# SUSTAINA-Power-Logging-Board.net
KiCad netlist of a schematic drawn in EAGLE
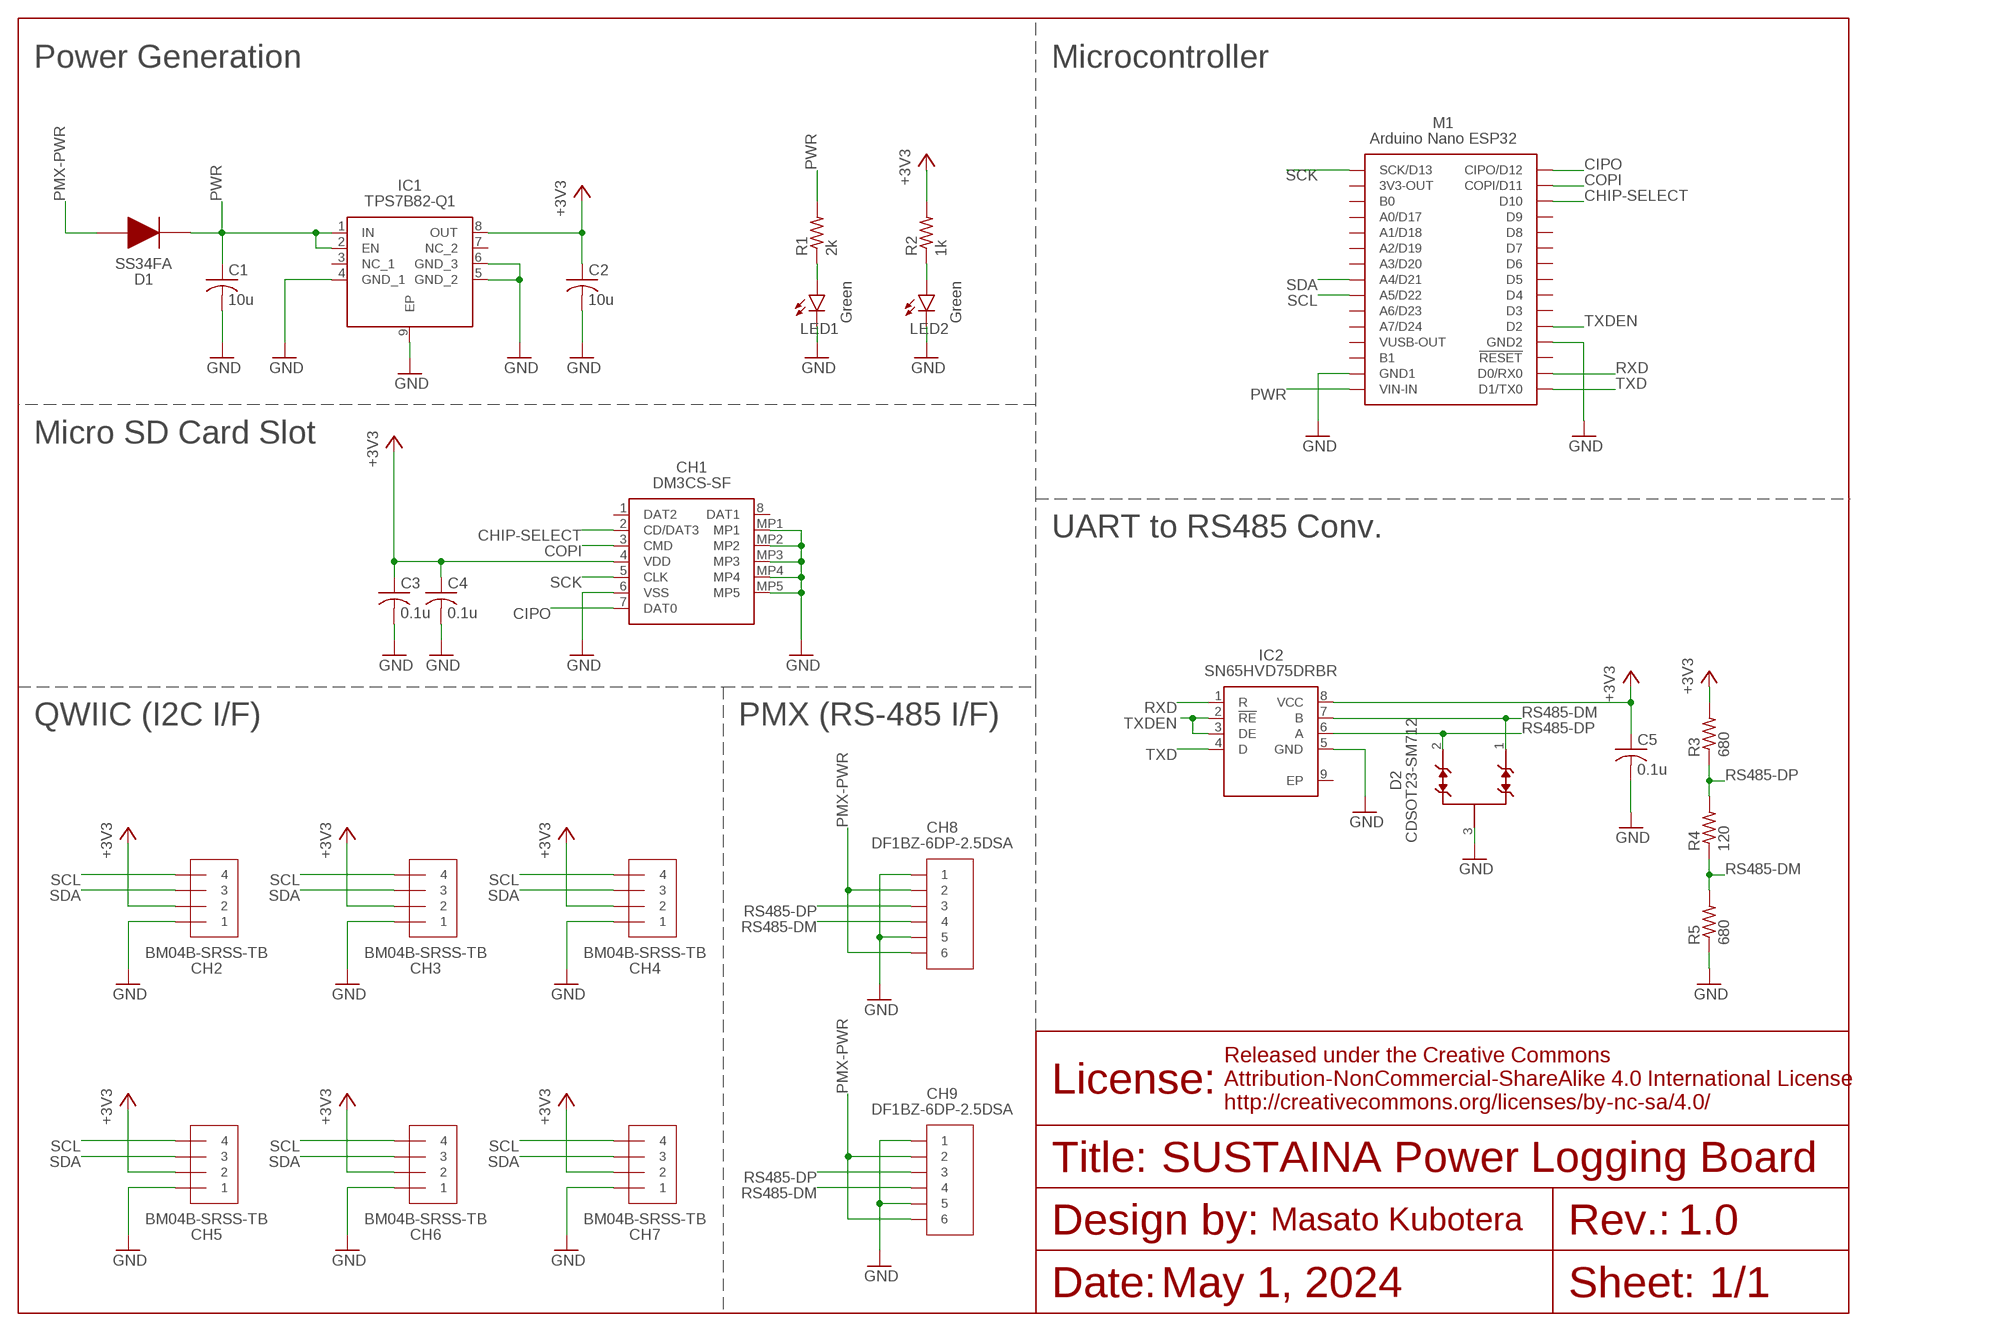
[diagram p0: schematic, sheet 1]

(export (version "E")
  (design (tool "Eeschema 10.0.6"))
  (components
    (comp (ref "C1")
      (value "10u")
      (footprint "eagle-import:C0603")
      (libsource (lib "eagle-import") (part "C-USC0603"))
    )
    (comp (ref "C2")
      (value "10u")
      (footprint "eagle-import:C0603")
      (libsource (lib "eagle-import") (part "C-USC0603"))
    )
    (comp (ref "C3")
      (value "0.1u")
      (footprint "eagle-import:C0603")
      (libsource (lib "eagle-import") (part "C-USC0603"))
    )
    (comp (ref "C4")
      (value "0.1u")
      (footprint "eagle-import:C0603")
      (libsource (lib "eagle-import") (part "C-USC0603"))
    )
    (comp (ref "C5")
      (value "0.1u")
      (footprint "eagle-import:C0603")
      (libsource (lib "eagle-import") (part "C-USC0603"))
    )
    (comp (ref "CH1")
      (value "DM3CS-SF")
      (footprint "eagle-import:DM3CS-SF")
      (libsource (lib "eagle-import") (part "DM3CS-SF"))
    )
    (comp (ref "CH2")
      (value "BM04B-SRSS-TB")
      (footprint "eagle-import:BM04B-SRSS-TB")
      (libsource (lib "eagle-import") (part "BM04B-SRSS-TB"))
    )
    (comp (ref "CH3")
      (value "BM04B-SRSS-TB")
      (footprint "eagle-import:BM04B-SRSS-TB")
      (libsource (lib "eagle-import") (part "BM04B-SRSS-TB"))
    )
    (comp (ref "CH4")
      (value "BM04B-SRSS-TB")
      (footprint "eagle-import:BM04B-SRSS-TB")
      (libsource (lib "eagle-import") (part "BM04B-SRSS-TB"))
    )
    (comp (ref "CH5")
      (value "BM04B-SRSS-TB")
      (footprint "eagle-import:BM04B-SRSS-TB")
      (libsource (lib "eagle-import") (part "BM04B-SRSS-TB"))
    )
    (comp (ref "CH6")
      (value "BM04B-SRSS-TB")
      (footprint "eagle-import:BM04B-SRSS-TB")
      (libsource (lib "eagle-import") (part "BM04B-SRSS-TB"))
    )
    (comp (ref "CH7")
      (value "BM04B-SRSS-TB")
      (footprint "eagle-import:BM04B-SRSS-TB")
      (libsource (lib "eagle-import") (part "BM04B-SRSS-TB"))
    )
    (comp (ref "CH8")
      (value "DF1BZ-6DP-25DSA")
      (footprint "eagle-import:DF1BZ-6DP-25DSA")
      (libsource (lib "eagle-import") (part "DF1BZ-6DP-25DSA"))
    )
    (comp (ref "CH9")
      (value "DF1BZ-6DP-25DSA")
      (footprint "eagle-import:DF1BZ-6DP-25DSA")
      (libsource (lib "eagle-import") (part "DF1BZ-6DP-25DSA"))
    )
    (comp (ref "D1")
      (value "SS34FA")
      (footprint "eagle-import:SS34FA")
      (libsource (lib "eagle-import") (part "SS34FA"))
    )
    (comp (ref "D2")
      (value "CDSOT23-SM712")
      (footprint "eagle-import:SOT-23-3")
      (libsource (lib "eagle-import") (part "CDSOT23-SM712"))
    )
    (comp (ref "IC1")
      (value "TPS7B82-Q1")
      (footprint "eagle-import:SOP65P490X110-9N")
      (libsource (lib "eagle-import") (part "TPS7B82-Q1"))
    )
    (comp (ref "IC2")
      (value "SN65HVD75DRBR")
      (footprint "eagle-import:SON65P300X300X100-9N")
      (libsource (lib "eagle-import") (part "SN65HVD75DRBR"))
    )
    (comp (ref "LED1")
      (value "Green")
      (footprint "eagle-import:SML0603")
      (libsource (lib "eagle-import") (part "LEDSML0603"))
    )
    (comp (ref "LED2")
      (value "Green")
      (footprint "eagle-import:SML0603")
      (libsource (lib "eagle-import") (part "LEDSML0603"))
    )
    (comp (ref "M1")
      (value "NANO-ESP32")
      (footprint "eagle-import:NANO-ESP32")
      (libsource (lib "eagle-import") (part "NANO-ESP32"))
    )
    (comp (ref "R1")
      (value "2k")
      (footprint "eagle-import:R0603")
      (libsource (lib "eagle-import") (part "R-US_R0603"))
    )
    (comp (ref "R2")
      (value "1k")
      (footprint "eagle-import:R0603")
      (libsource (lib "eagle-import") (part "R-US_R0603"))
    )
    (comp (ref "R3")
      (value "680")
      (footprint "eagle-import:R0603")
      (libsource (lib "eagle-import") (part "R-US_R0603"))
    )
    (comp (ref "R4")
      (value "120")
      (footprint "eagle-import:R0603")
      (libsource (lib "eagle-import") (part "R-US_R0603"))
    )
    (comp (ref "R5")
      (value "680")
      (footprint "eagle-import:R0603")
      (libsource (lib "eagle-import") (part "R-US_R0603"))
    )
  )
  (nets
    (net (code "1") (name "+3V3") (class "Default")
      (node (ref "C2") (pin "1") (pinfunction "1_1") (pintype "passive"))
      (node (ref "C3") (pin "1") (pinfunction "1_1") (pintype "passive"))
      (node (ref "C4") (pin "1") (pinfunction "1_1") (pintype "passive"))
      (node (ref "C5") (pin "1") (pinfunction "1_1") (pintype "passive"))
      (node (ref "CH1") (pin "4") (pinfunction "VDD_4") (pintype "bidirectional"))
      (node (ref "CH2") (pin "2") (pinfunction "2_2") (pintype "bidirectional"))
      (node (ref "CH3") (pin "2") (pinfunction "2_2") (pintype "bidirectional"))
      (node (ref "CH4") (pin "2") (pinfunction "2_2") (pintype "bidirectional"))
      (node (ref "CH5") (pin "2") (pinfunction "2_2") (pintype "bidirectional"))
      (node (ref "CH6") (pin "2") (pinfunction "2_2") (pintype "bidirectional"))
      (node (ref "CH7") (pin "2") (pinfunction "2_2") (pintype "bidirectional"))
      (node (ref "IC1") (pin "8") (pinfunction "OUT_8") (pintype "bidirectional"))
      (node (ref "IC2") (pin "8") (pinfunction "VCC_8") (pintype "bidirectional"))
      (node (ref "R2") (pin "2") (pinfunction "2_2") (pintype "passive"))
      (node (ref "R3") (pin "2") (pinfunction "2_2") (pintype "passive"))
    )
    (net (code "2") (name "/CHIP-SELECT") (class "Default")
      (node (ref "CH1") (pin "2") (pinfunction "CD/DAT3_2") (pintype "bidirectional"))
      (node (ref "M1") (pin "D10") (pinfunction "D10_D10") (pintype "bidirectional"))
    )
    (net (code "3") (name "/CIPO") (class "Default")
      (node (ref "CH1") (pin "7") (pinfunction "DAT0_7") (pintype "bidirectional"))
      (node (ref "M1") (pin "CIPO/D12") (pinfunction "CIPO/D12_CIPO/D12") (pintype "bidirectional"))
    )
    (net (code "4") (name "/COPI") (class "Default")
      (node (ref "CH1") (pin "3") (pinfunction "CMD_3") (pintype "bidirectional"))
      (node (ref "M1") (pin "COPI/D11") (pinfunction "COPI/D11_COPI/D11") (pintype "bidirectional"))
    )
    (net (code "5") (name "/PMX-PWR") (class "Default")
      (node (ref "CH8") (pin "2") (pinfunction "2_2") (pintype "bidirectional"))
      (node (ref "CH8") (pin "6") (pinfunction "6_6") (pintype "bidirectional"))
      (node (ref "CH9") (pin "2") (pinfunction "2_2") (pintype "bidirectional"))
      (node (ref "CH9") (pin "6") (pinfunction "6_6") (pintype "bidirectional"))
      (node (ref "D1") (pin "2") (pinfunction "2_2") (pintype "bidirectional"))
    )
    (net (code "6") (name "/PWR") (class "Default")
      (node (ref "C1") (pin "1") (pinfunction "1_1") (pintype "passive"))
      (node (ref "D1") (pin "1") (pinfunction "1_1") (pintype "bidirectional"))
      (node (ref "IC1") (pin "1") (pinfunction "IN_1") (pintype "bidirectional"))
      (node (ref "IC1") (pin "2") (pinfunction "EN_2") (pintype "bidirectional"))
      (node (ref "M1") (pin "VIN-IN") (pinfunction "VIN-IN_VIN-IN") (pintype "bidirectional"))
      (node (ref "R1") (pin "2") (pinfunction "2_2") (pintype "passive"))
    )
    (net (code "7") (name "/RS485-DM") (class "Default")
      (node (ref "CH8") (pin "4") (pinfunction "4_4") (pintype "bidirectional"))
      (node (ref "CH9") (pin "4") (pinfunction "4_4") (pintype "bidirectional"))
      (node (ref "D2") (pin "1") (pinfunction "1_1") (pintype "bidirectional"))
      (node (ref "IC2") (pin "7") (pinfunction "B_7") (pintype "bidirectional"))
      (node (ref "R4") (pin "1") (pinfunction "1_1") (pintype "passive"))
      (node (ref "R5") (pin "2") (pinfunction "2_2") (pintype "passive"))
    )
    (net (code "8") (name "/RS485-DP") (class "Default")
      (node (ref "CH8") (pin "3") (pinfunction "3_3") (pintype "bidirectional"))
      (node (ref "CH9") (pin "3") (pinfunction "3_3") (pintype "bidirectional"))
      (node (ref "D2") (pin "2") (pinfunction "2_2") (pintype "bidirectional"))
      (node (ref "IC2") (pin "6") (pinfunction "A_6") (pintype "bidirectional"))
      (node (ref "R3") (pin "1") (pinfunction "1_1") (pintype "passive"))
      (node (ref "R4") (pin "2") (pinfunction "2_2") (pintype "passive"))
    )
    (net (code "9") (name "/RXD") (class "Default")
      (node (ref "IC2") (pin "1") (pinfunction "R_1") (pintype "bidirectional"))
      (node (ref "M1") (pin "D0/RX0") (pinfunction "D0/RX0_D0/RX0") (pintype "bidirectional"))
    )
    (net (code "10") (name "/SCK") (class "Default")
      (node (ref "CH1") (pin "5") (pinfunction "CLK_5") (pintype "bidirectional"))
      (node (ref "M1") (pin "SCK/D13") (pinfunction "SCK/D13_SCK/D13") (pintype "bidirectional"))
    )
    (net (code "11") (name "/SCL") (class "Default")
      (node (ref "CH2") (pin "4") (pinfunction "4_4") (pintype "bidirectional"))
      (node (ref "CH3") (pin "4") (pinfunction "4_4") (pintype "bidirectional"))
      (node (ref "CH4") (pin "4") (pinfunction "4_4") (pintype "bidirectional"))
      (node (ref "CH5") (pin "4") (pinfunction "4_4") (pintype "bidirectional"))
      (node (ref "CH6") (pin "4") (pinfunction "4_4") (pintype "bidirectional"))
      (node (ref "CH7") (pin "4") (pinfunction "4_4") (pintype "bidirectional"))
      (node (ref "M1") (pin "A5/D22") (pinfunction "A5/D22_A5/D22") (pintype "bidirectional"))
    )
    (net (code "12") (name "/SDA") (class "Default")
      (node (ref "CH2") (pin "3") (pinfunction "3_3") (pintype "bidirectional"))
      (node (ref "CH3") (pin "3") (pinfunction "3_3") (pintype "bidirectional"))
      (node (ref "CH4") (pin "3") (pinfunction "3_3") (pintype "bidirectional"))
      (node (ref "CH5") (pin "3") (pinfunction "3_3") (pintype "bidirectional"))
      (node (ref "CH6") (pin "3") (pinfunction "3_3") (pintype "bidirectional"))
      (node (ref "CH7") (pin "3") (pinfunction "3_3") (pintype "bidirectional"))
      (node (ref "M1") (pin "A4/D21") (pinfunction "A4/D21_A4/D21") (pintype "bidirectional"))
    )
    (net (code "13") (name "/TXD") (class "Default")
      (node (ref "IC2") (pin "4") (pinfunction "D_4") (pintype "bidirectional"))
      (node (ref "M1") (pin "D1/TX0") (pinfunction "D1/TX0_D1/TX0") (pintype "bidirectional"))
    )
    (net (code "14") (name "/TXDEN") (class "Default")
      (node (ref "IC2") (pin "2") (pinfunction "~{RE}_2") (pintype "bidirectional"))
      (node (ref "IC2") (pin "3") (pinfunction "DE_3") (pintype "bidirectional"))
      (node (ref "M1") (pin "D2") (pinfunction "D2_D2") (pintype "bidirectional"))
    )
    (net (code "15") (name "GND") (class "Default")
      (node (ref "C1") (pin "2") (pinfunction "2_2") (pintype "passive"))
      (node (ref "C2") (pin "2") (pinfunction "2_2") (pintype "passive"))
      (node (ref "C3") (pin "2") (pinfunction "2_2") (pintype "passive"))
      (node (ref "C4") (pin "2") (pinfunction "2_2") (pintype "passive"))
      (node (ref "C5") (pin "2") (pinfunction "2_2") (pintype "passive"))
      (node (ref "CH1") (pin "6") (pinfunction "VSS_6") (pintype "bidirectional"))
      (node (ref "CH1") (pin "MP1") (pinfunction "MP1_MP1") (pintype "bidirectional"))
      (node (ref "CH1") (pin "MP2") (pinfunction "MP2_MP2") (pintype "bidirectional"))
      (node (ref "CH1") (pin "MP3") (pinfunction "MP3_MP3") (pintype "bidirectional"))
      (node (ref "CH1") (pin "MP4") (pinfunction "MP4_MP4") (pintype "bidirectional"))
      (node (ref "CH1") (pin "MP5") (pinfunction "MP5_MP5") (pintype "bidirectional"))
      (node (ref "CH2") (pin "1") (pinfunction "1_1") (pintype "bidirectional"))
      (node (ref "CH3") (pin "1") (pinfunction "1_1") (pintype "bidirectional"))
      (node (ref "CH4") (pin "1") (pinfunction "1_1") (pintype "bidirectional"))
      (node (ref "CH5") (pin "1") (pinfunction "1_1") (pintype "bidirectional"))
      (node (ref "CH6") (pin "1") (pinfunction "1_1") (pintype "bidirectional"))
      (node (ref "CH7") (pin "1") (pinfunction "1_1") (pintype "bidirectional"))
      (node (ref "CH8") (pin "1") (pinfunction "1_1") (pintype "bidirectional"))
      (node (ref "CH8") (pin "5") (pinfunction "5_5") (pintype "bidirectional"))
      (node (ref "CH9") (pin "1") (pinfunction "1_1") (pintype "bidirectional"))
      (node (ref "CH9") (pin "5") (pinfunction "5_5") (pintype "bidirectional"))
      (node (ref "D2") (pin "3") (pinfunction "3_3") (pintype "bidirectional"))
      (node (ref "IC1") (pin "4") (pinfunction "GND_1_4") (pintype "bidirectional"))
      (node (ref "IC1") (pin "5") (pinfunction "GND_2_5") (pintype "bidirectional"))
      (node (ref "IC1") (pin "6") (pinfunction "GND_3_6") (pintype "bidirectional"))
      (node (ref "IC1") (pin "9") (pinfunction "EP_9") (pintype "bidirectional"))
      (node (ref "IC2") (pin "5") (pinfunction "GND_5") (pintype "bidirectional"))
      (node (ref "LED1") (pin "C") (pinfunction "C_C") (pintype "passive"))
      (node (ref "LED2") (pin "C") (pinfunction "C_C") (pintype "passive"))
      (node (ref "M1") (pin "GND1") (pinfunction "GND1_GND1") (pintype "bidirectional"))
      (node (ref "M1") (pin "GND2") (pinfunction "GND2_GND2") (pintype "bidirectional"))
      (node (ref "R5") (pin "1") (pinfunction "1_1") (pintype "passive"))
    )
    (net (code "16") (name "Net-(LED1-PadA)") (class "Default")
      (node (ref "LED1") (pin "A") (pinfunction "A_A") (pintype "passive"))
      (node (ref "R1") (pin "1") (pinfunction "1_1") (pintype "passive"))
    )
    (net (code "17") (name "Net-(LED2-PadA)") (class "Default")
      (node (ref "LED2") (pin "A") (pinfunction "A_A") (pintype "passive"))
      (node (ref "R2") (pin "1") (pinfunction "1_1") (pintype "passive"))
    )
    (net (code "18") (name "unconnected-(CH1-DAT1-Pad8)") (class "Default")
      (node (ref "CH1") (pin "8") (pinfunction "DAT1_8") (pintype "bidirectional"))
    )
    (net (code "19") (name "unconnected-(CH1-DAT2-Pad1)") (class "Default")
      (node (ref "CH1") (pin "1") (pinfunction "DAT2_1") (pintype "bidirectional"))
    )
    (net (code "20") (name "unconnected-(IC1-NC_1-Pad3)") (class "Default")
      (node (ref "IC1") (pin "3") (pinfunction "NC_1_3") (pintype "no_connect"))
    )
    (net (code "21") (name "unconnected-(IC1-NC_2-Pad7)") (class "Default")
      (node (ref "IC1") (pin "7") (pinfunction "NC_2_7") (pintype "no_connect"))
    )
    (net (code "22") (name "unconnected-(IC2-EP-Pad9)") (class "Default")
      (node (ref "IC2") (pin "9") (pinfunction "EP_9") (pintype "bidirectional"))
    )
    (net (code "23") (name "unconnected-(M1-Pad3V3-OUT)") (class "Default")
      (node (ref "M1") (pin "3V3-OUT") (pinfunction "3V3-OUT_3V3-OUT") (pintype "bidirectional"))
    )
    (net (code "24") (name "unconnected-(M1-PadA0{slash}D17)") (class "Default")
      (node (ref "M1") (pin "A0/D17") (pinfunction "A0/D17_A0/D17") (pintype "bidirectional"))
    )
    (net (code "25") (name "unconnected-(M1-PadA1{slash}D18)") (class "Default")
      (node (ref "M1") (pin "A1/D18") (pinfunction "A1/D18_A1/D18") (pintype "bidirectional"))
    )
    (net (code "26") (name "unconnected-(M1-PadA2{slash}D19)") (class "Default")
      (node (ref "M1") (pin "A2/D19") (pinfunction "A2/D19_A2/D19") (pintype "bidirectional"))
    )
    (net (code "27") (name "unconnected-(M1-PadA3{slash}D20)") (class "Default")
      (node (ref "M1") (pin "A3/D20") (pinfunction "A3/D20_A3/D20") (pintype "bidirectional"))
    )
    (net (code "28") (name "unconnected-(M1-PadA6{slash}D23)") (class "Default")
      (node (ref "M1") (pin "A6/D23") (pinfunction "A6/D23_A6/D23") (pintype "bidirectional"))
    )
    (net (code "29") (name "unconnected-(M1-PadA7{slash}D24)") (class "Default")
      (node (ref "M1") (pin "A7/D24") (pinfunction "A7/D24_A7/D24") (pintype "bidirectional"))
    )
    (net (code "30") (name "unconnected-(M1-PadB0)") (class "Default")
      (node (ref "M1") (pin "B0") (pinfunction "B0_B0") (pintype "bidirectional"))
    )
    (net (code "31") (name "unconnected-(M1-PadB1)") (class "Default")
      (node (ref "M1") (pin "B1") (pinfunction "B1_B1") (pintype "bidirectional"))
    )
    (net (code "32") (name "unconnected-(M1-PadD3)") (class "Default")
      (node (ref "M1") (pin "D3") (pinfunction "D3_D3") (pintype "bidirectional"))
    )
    (net (code "33") (name "unconnected-(M1-PadD4)") (class "Default")
      (node (ref "M1") (pin "D4") (pinfunction "D4_D4") (pintype "bidirectional"))
    )
    (net (code "34") (name "unconnected-(M1-PadD5)") (class "Default")
      (node (ref "M1") (pin "D5") (pinfunction "D5_D5") (pintype "bidirectional"))
    )
    (net (code "35") (name "unconnected-(M1-PadD6)") (class "Default")
      (node (ref "M1") (pin "D6") (pinfunction "D6_D6") (pintype "bidirectional"))
    )
    (net (code "36") (name "unconnected-(M1-PadD7)") (class "Default")
      (node (ref "M1") (pin "D7") (pinfunction "D7_D7") (pintype "bidirectional"))
    )
    (net (code "37") (name "unconnected-(M1-PadD8)") (class "Default")
      (node (ref "M1") (pin "D8") (pinfunction "D8_D8") (pintype "bidirectional"))
    )
    (net (code "38") (name "unconnected-(M1-PadD9)") (class "Default")
      (node (ref "M1") (pin "D9") (pinfunction "D9_D9") (pintype "bidirectional"))
    )
    (net (code "39") (name "unconnected-(M1-PadVUSB-OUT)") (class "Default")
      (node (ref "M1") (pin "VUSB-OUT") (pinfunction "VUSB-OUT_VUSB-OUT") (pintype "bidirectional"))
    )
    (net (code "40") (name "unconnected-(M1-~{RESET}-Pad!RESET)") (class "Default")
      (node (ref "M1") (pin "!RESET") (pinfunction "~{RESET}_!RESET") (pintype "bidirectional"))
    )
  )
)
